# breakout.net
KiCad netlist of a schematic drawn in EAGLE
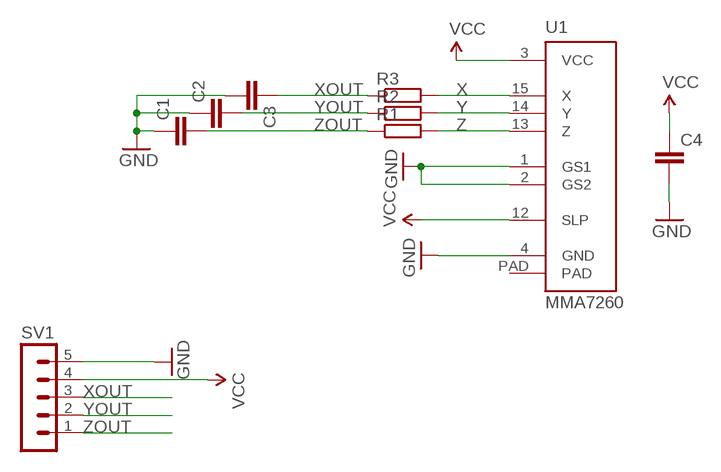
[diagram p0: schematic, sheet 1]

(export (version "E")
  (design (tool "Eeschema 10.0.6"))
  (components
    (comp (ref "C1")
      (value "C-EUC1206")
      (footprint "eagle-import:C1206")
      (libsource (lib "eagle-import") (part "C-EUC1206"))
    )
    (comp (ref "C2")
      (value "C-EUC1206")
      (footprint "eagle-import:C1206")
      (libsource (lib "eagle-import") (part "C-EUC1206"))
    )
    (comp (ref "C3")
      (value "C-EUC1206")
      (footprint "eagle-import:C1206")
      (libsource (lib "eagle-import") (part "C-EUC1206"))
    )
    (comp (ref "C4")
      (value "C-EUC1206")
      (footprint "eagle-import:C1206")
      (libsource (lib "eagle-import") (part "C-EUC1206"))
    )
    (comp (ref "R1")
      (value "R-EU_R1206")
      (footprint "eagle-import:R1206")
      (libsource (lib "eagle-import") (part "R-EU_R1206"))
    )
    (comp (ref "R2")
      (value "R-EU_R1206")
      (footprint "eagle-import:R1206")
      (libsource (lib "eagle-import") (part "R-EU_R1206"))
    )
    (comp (ref "R3")
      (value "R-EU_R1206")
      (footprint "eagle-import:R1206")
      (libsource (lib "eagle-import") (part "R-EU_R1206"))
    )
    (comp (ref "SV1")
      (value "MA05-1")
      (footprint "eagle-import:MA05-1")
      (libsource (lib "eagle-import") (part "MA05-1"))
    )
    (comp (ref "U1")
      (value "MMA7260")
      (footprint "eagle-import:MMA7260")
      (libsource (lib "eagle-import") (part "MMA7260"))
    )
  )
  (nets
    (net (code "1") (name "/X") (class "Default")
      (node (ref "R3") (pin "2") (pinfunction "2_2") (pintype "passive"))
      (node (ref "U1") (pin "15") (pinfunction "X_15") (pintype "bidirectional"))
    )
    (net (code "2") (name "/XOUT") (class "Default")
      (node (ref "C3") (pin "1") (pinfunction "1_1") (pintype "passive"))
      (node (ref "R3") (pin "1") (pinfunction "1_1") (pintype "passive"))
      (node (ref "SV1") (pin "3") (pinfunction "3_3") (pintype "passive"))
    )
    (net (code "3") (name "/Y") (class "Default")
      (node (ref "R2") (pin "2") (pinfunction "2_2") (pintype "passive"))
      (node (ref "U1") (pin "14") (pinfunction "Y_14") (pintype "bidirectional"))
    )
    (net (code "4") (name "/YOUT") (class "Default")
      (node (ref "C2") (pin "2") (pinfunction "2_2") (pintype "passive"))
      (node (ref "R2") (pin "1") (pinfunction "1_1") (pintype "passive"))
      (node (ref "SV1") (pin "2") (pinfunction "2_2") (pintype "passive"))
    )
    (net (code "5") (name "/Z") (class "Default")
      (node (ref "R1") (pin "2") (pinfunction "2_2") (pintype "passive"))
      (node (ref "U1") (pin "13") (pinfunction "Z_13") (pintype "bidirectional"))
    )
    (net (code "6") (name "/ZOUT") (class "Default")
      (node (ref "C1") (pin "2") (pinfunction "2_2") (pintype "passive"))
      (node (ref "R1") (pin "1") (pinfunction "1_1") (pintype "passive"))
      (node (ref "SV1") (pin "1") (pinfunction "1_1") (pintype "passive"))
    )
    (net (code "7") (name "GND") (class "Default")
      (node (ref "C1") (pin "1") (pinfunction "1_1") (pintype "passive"))
      (node (ref "C2") (pin "1") (pinfunction "1_1") (pintype "passive"))
      (node (ref "C3") (pin "2") (pinfunction "2_2") (pintype "passive"))
      (node (ref "C4") (pin "2") (pinfunction "2_2") (pintype "passive"))
      (node (ref "SV1") (pin "5") (pinfunction "5_5") (pintype "passive"))
      (node (ref "U1") (pin "1") (pinfunction "GS1_1") (pintype "bidirectional"))
      (node (ref "U1") (pin "2") (pinfunction "GS2_2") (pintype "bidirectional"))
      (node (ref "U1") (pin "4") (pinfunction "GND_4") (pintype "bidirectional"))
    )
    (net (code "8") (name "VCC") (class "Default")
      (node (ref "C4") (pin "1") (pinfunction "1_1") (pintype "passive"))
      (node (ref "SV1") (pin "4") (pinfunction "4_4") (pintype "passive"))
      (node (ref "U1") (pin "12") (pinfunction "SLP_12") (pintype "bidirectional"))
      (node (ref "U1") (pin "3") (pinfunction "VCC_3") (pintype "bidirectional"))
    )
    (net (code "9") (name "unconnected-(U1-PadPAD)") (class "Default")
      (node (ref "U1") (pin "PAD") (pinfunction "PAD_PAD") (pintype "bidirectional"))
    )
  )
)
